# SCH_Onboard-Card_2025-02-03.net
KiCad netlist of a schematic drawn in EasyEDA
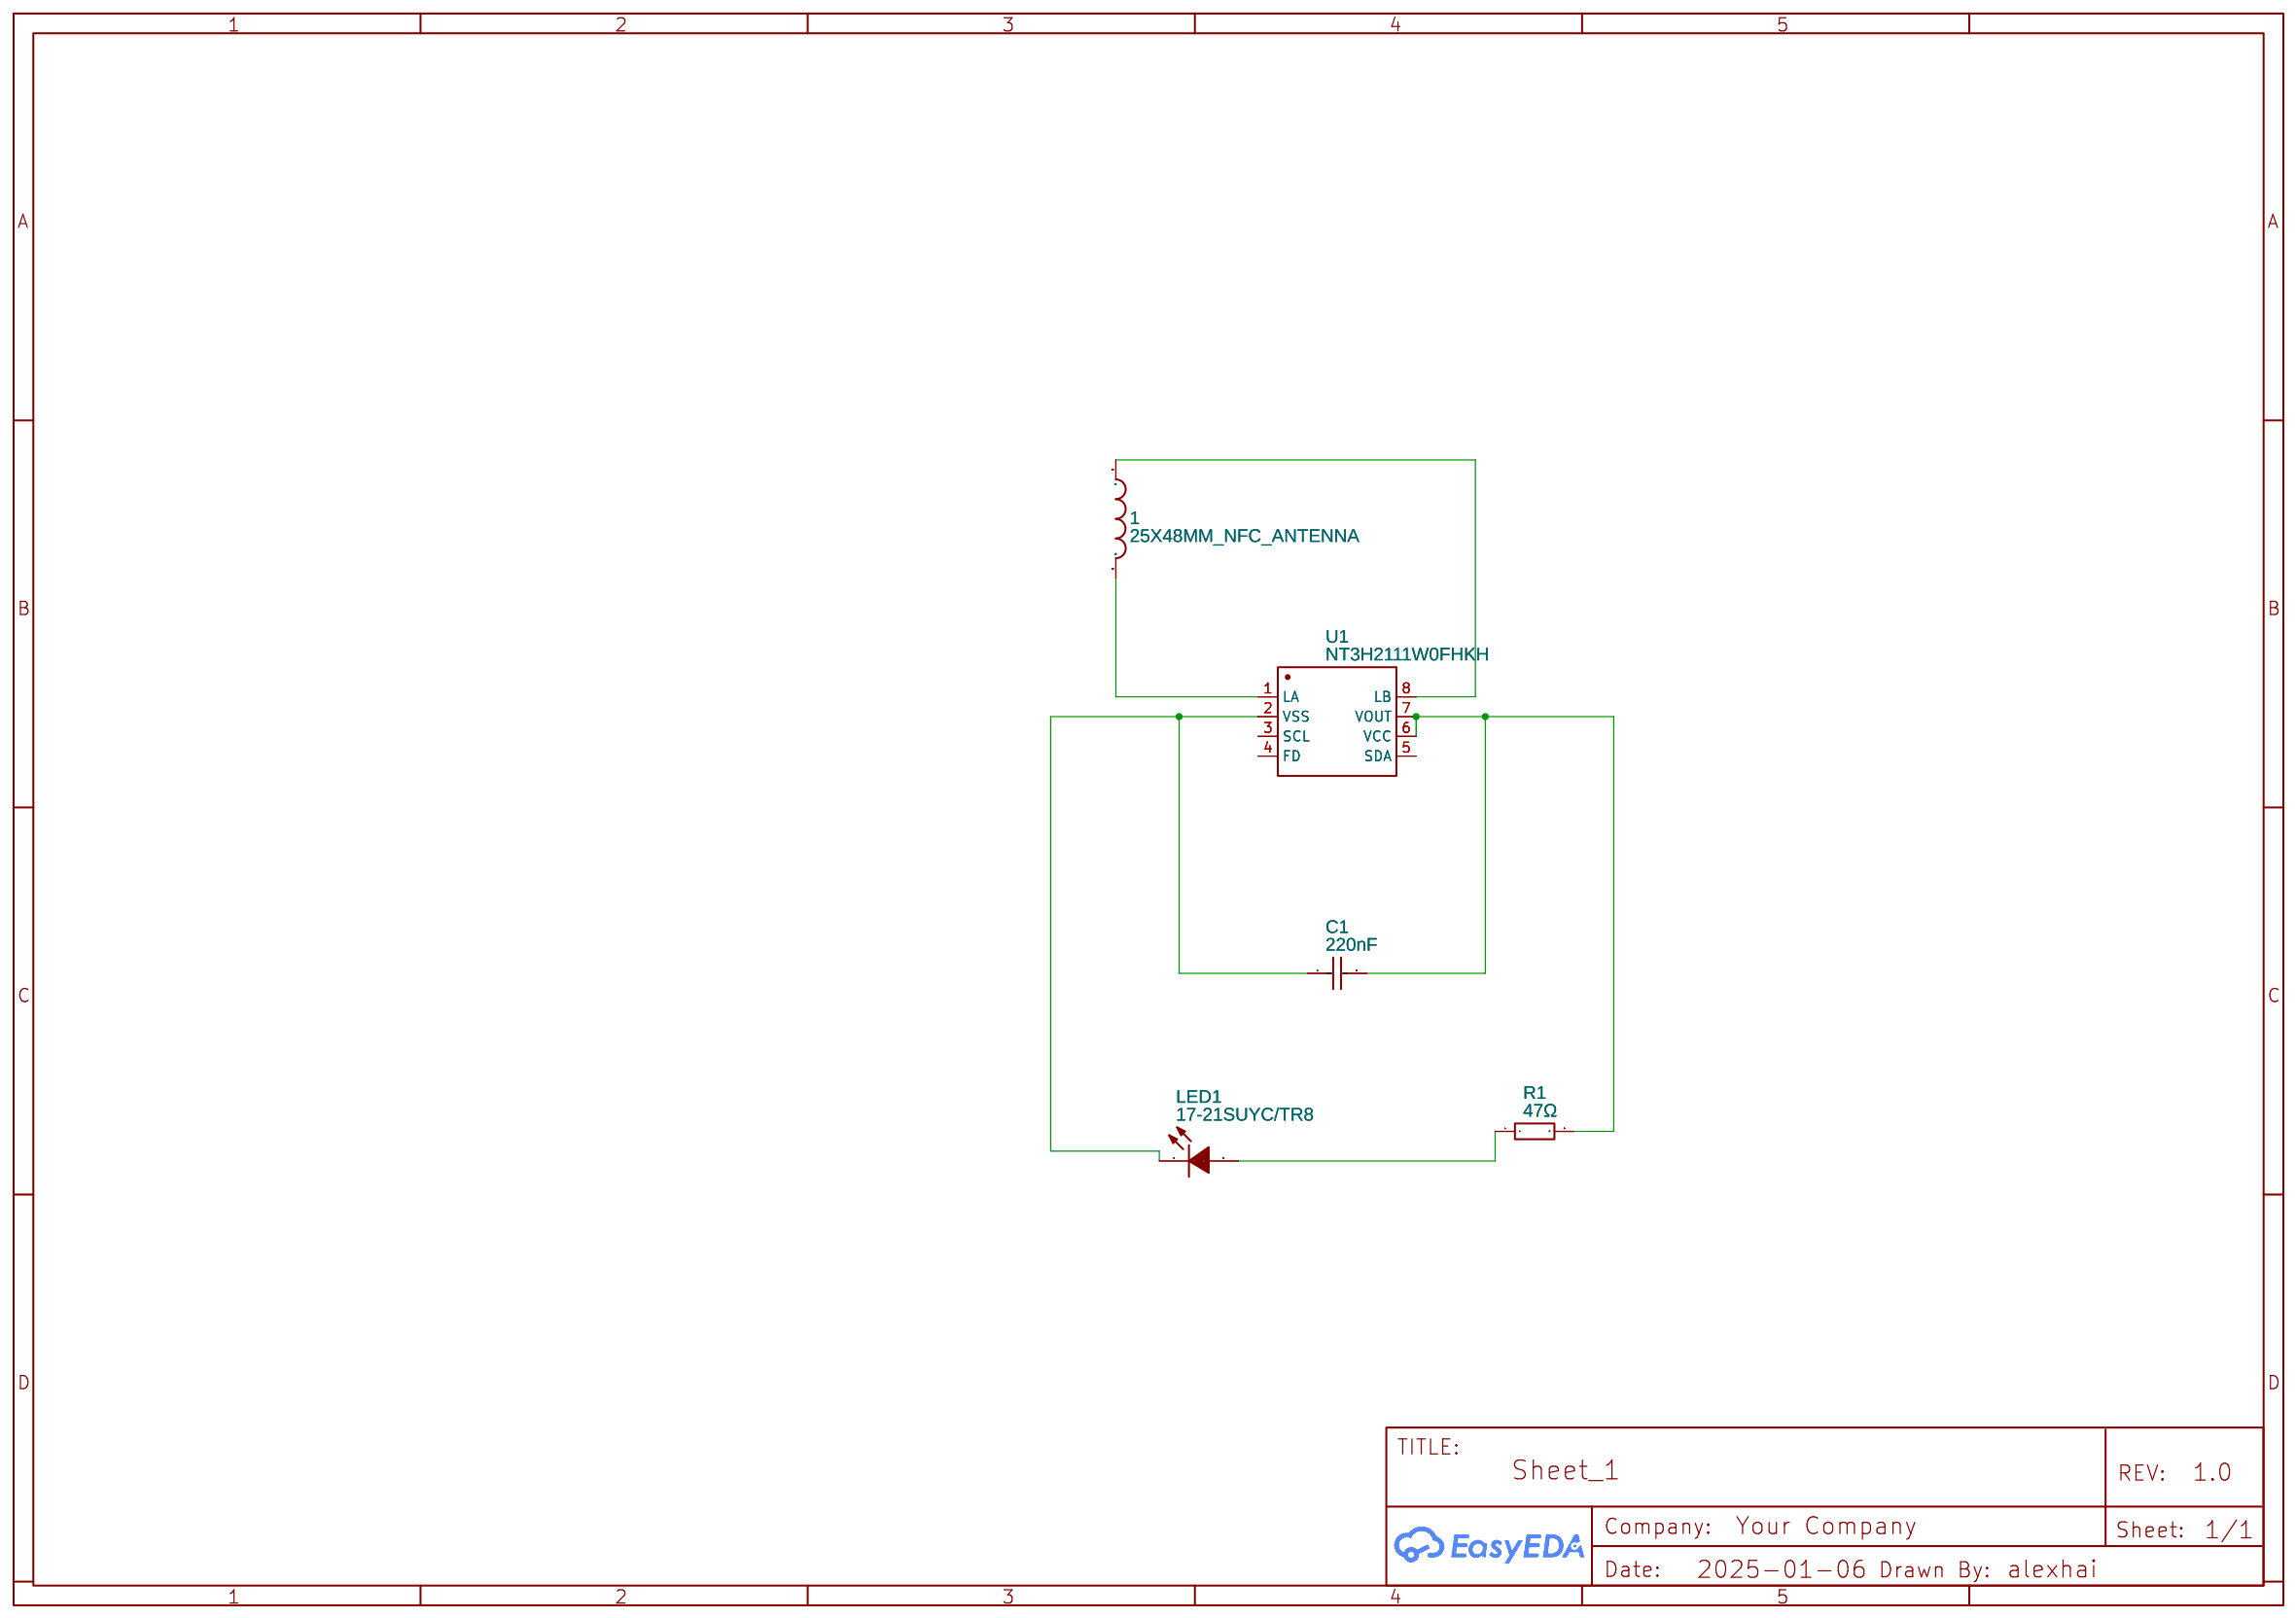
[diagram p0: schematic sheet]

(export (version "E")
  (design (tool "Eeschema 10.0.6"))
  (components
    (comp (ref "1") (value "25X48MM_NFC_ANTENNA") (libsource (lib "") (part "25X48MM_NFC_ANTENNA")))
    (comp (ref "C1")
      (value "220nF")
      (fields
        (field (name "Manufacturer Part") "CL10B224KA8NNNC")
        (field (name "Manufacturer") "SAMSUNG(三星)")
      )
      (libsource (lib "") (part "CL10B224KA8NNNC"))
    )
    (comp (ref "LED1")
      (value "17-21SUYC/TR8")
      (fields (field (name "Manufacturer Part") "KT-0805黄灯") (field (name "Manufacturer") "KENTO"))
      (libsource (lib "") (part "17-21SUYC/TR8"))
    )
    (comp (ref "R1")
      (value "47Ω")
      (fields
        (field (name "Manufacturer Part") "0603WAF470JT5E")
        (field (name "Manufacturer") "UNI-ROYAL(厚声)")
      )
      (libsource (lib "") (part "0603WAF470JT5E"))
    )
    (comp (ref "U1")
      (value "NT3H2111W0FHKH")
      (fields (field (name "Manufacturer") "NXP(恩智浦)"))
      (libsource (lib "") (part "NT3H2111W0FHKH"))
    )
  )
  (nets
    (net (code "1") (name "Net-(LED1-+)") (class "Default")
      (node (ref "LED1") (pin "1") (pinfunction "+_1") (pintype "unspecified"))
      (node (ref "R1") (pin "1") (pinfunction "1_1") (pintype "input"))
    )
    (net (code "2") (name "Net-(LED1--)") (class "Default")
      (node (ref "C1") (pin "1") (pinfunction "1_1") (pintype "input"))
      (node (ref "LED1") (pin "2") (pinfunction "-_2") (pintype "unspecified"))
      (node (ref "U1") (pin "2") (pinfunction "VSS_2") (pintype "unspecified"))
    )
    (net (code "3") (name "Net-(U1-LA)") (class "Default")
      (node (ref "1") (pin "P$2") (pinfunction "P$2_P$2") (pintype "bidirectional"))
      (node (ref "U1") (pin "1") (pinfunction "LA_1") (pintype "unspecified"))
    )
    (net (code "4") (name "Net-(U1-LB)") (class "Default")
      (node (ref "1") (pin "P$1") (pinfunction "P$1_P$1") (pintype "bidirectional"))
      (node (ref "U1") (pin "8") (pinfunction "LB_8") (pintype "unspecified"))
    )
    (net (code "5") (name "Net-(U1-VCC)") (class "Default")
      (node (ref "C1") (pin "2") (pinfunction "2_2") (pintype "input"))
      (node (ref "R1") (pin "2") (pinfunction "2_2") (pintype "input"))
      (node (ref "U1") (pin "6") (pinfunction "VCC_6") (pintype "unspecified"))
      (node (ref "U1") (pin "7") (pinfunction "VOUT_7") (pintype "unspecified"))
    )
    (net (code "6") (name "unconnected-(U1-FD-Pad4)") (class "Default")
      (node (ref "U1") (pin "4") (pinfunction "FD_4") (pintype "unspecified"))
    )
    (net (code "7") (name "unconnected-(U1-SCL-Pad3)") (class "Default")
      (node (ref "U1") (pin "3") (pinfunction "SCL_3") (pintype "unspecified"))
    )
    (net (code "8") (name "unconnected-(U1-SDA-Pad5)") (class "Default")
      (node (ref "U1") (pin "5") (pinfunction "SDA_5") (pintype "unspecified"))
    )
  )
)
